# PiTopUSBHub_UB.net
KiCad netlist of a schematic drawn in Altium Designer
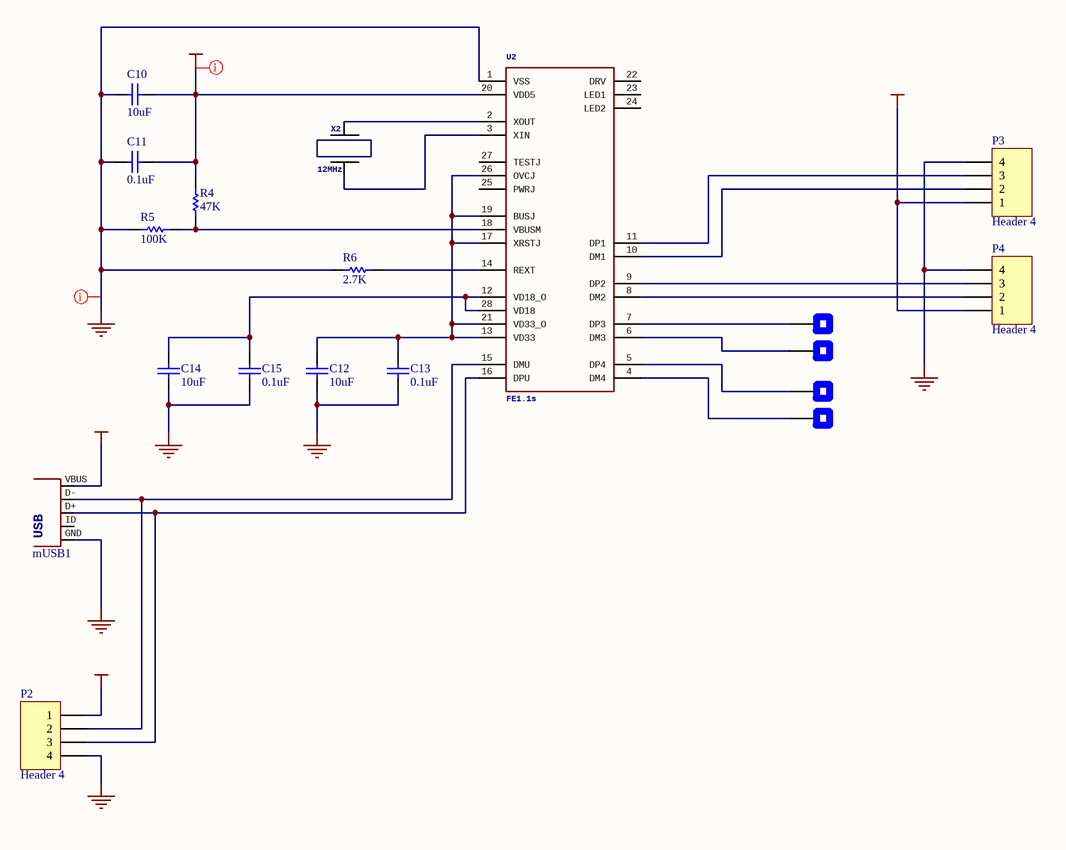
[diagram p0: PiTopUSBHub_UB.SchDoc]

(export (version "E")
  (design (tool "Eeschema 10.0.6"))
  (components
    (comp (ref "C10")
      (value "10uF")
      (footprint "C0805")
      (description "Ceramic Chip Capacitor - Standard")
      (fields (field (name "Comment") "C0805") (field (name "PUBLISHER") "Altium Limited"))
      (libsource (lib "KEMET Chip Capacitor") (part "C0805"))
    )
    (comp (ref "C11")
      (value "0.1uF")
      (footprint "C0805")
      (description "Ceramic Chip Capacitor - Standard")
      (fields (field (name "Comment") "C0805") (field (name "PUBLISHER") "Altium Limited"))
      (libsource (lib "KEMET Chip Capacitor") (part "C0805"))
    )
    (comp (ref "C12")
      (value "10uF")
      (footprint "C0805")
      (description "Ceramic Chip Capacitor - Standard")
      (fields (field (name "Comment") "C0805") (field (name "PUBLISHER") "Altium Limited"))
      (libsource (lib "KEMET Chip Capacitor") (part "C0805"))
    )
    (comp (ref "C13")
      (value "0.1uF")
      (footprint "C0805")
      (description "Ceramic Chip Capacitor - Standard")
      (fields (field (name "Comment") "C0805") (field (name "PUBLISHER") "Altium Limited"))
      (libsource (lib "KEMET Chip Capacitor") (part "C0805"))
    )
    (comp (ref "C14")
      (value "10uF")
      (footprint "C0805")
      (description "Ceramic Chip Capacitor - Standard")
      (fields (field (name "Comment") "C0805") (field (name "PUBLISHER") "Altium Limited"))
      (libsource (lib "KEMET Chip Capacitor") (part "C0805"))
    )
    (comp (ref "C15")
      (value "0.1uF")
      (footprint "C0805")
      (description "Ceramic Chip Capacitor - Standard")
      (fields (field (name "Comment") "C0805") (field (name "PUBLISHER") "Altium Limited"))
      (libsource (lib "KEMET Chip Capacitor") (part "C0805"))
    )
    (comp (ref "mUSB1")
      (value "miniUSB-PTH")
      (footprint "miniUSB-F-PTH")
      (fields (field (name "USB") "USB"))
      (libsource (lib "lib") (part "miniUSBA-PTH"))
    )
    (comp (ref "P2")
      (value "Header 4")
      (footprint "HDR1X4")
      (description "Header, 4-Pin")
      (fields (field (name "PUBLISHER") "Altium Limited"))
      (libsource (lib "") (part "Header 4_1"))
    )
    (comp (ref "P3")
      (value "Header 4")
      (footprint "HDR1X4")
      (description "Header, 4-Pin")
      (fields (field (name "PUBLISHER") "Altium Limited"))
      (libsource (lib "Miscellaneous Connectors") (part "Header 4"))
    )
    (comp (ref "P4")
      (value "Header 4")
      (footprint "HDR1X4")
      (description "Header, 4-Pin")
      (fields (field (name "PUBLISHER") "Altium Limited"))
      (libsource (lib "Miscellaneous Connectors") (part "Header 4"))
    )
    (comp (ref "R4")
      (value "47K")
      (footprint "R0805")
      (fields (field (name "PUBLISHER") "Altium Limited"))
      (libsource (lib "lib") (part "R0805"))
    )
    (comp (ref "R5")
      (value "100K")
      (footprint "R0805")
      (fields (field (name "PUBLISHER") "Altium Limited"))
      (libsource (lib "lib") (part "R0805"))
    )
    (comp (ref "R6")
      (value "2.7K")
      (footprint "R0805")
      (fields (field (name "PUBLISHER") "Altium Limited"))
      (libsource (lib "lib") (part "R0805"))
    )
    (comp (ref "TP1") (value "TP") (footprint "TP") (libsource (lib "lib") (part "TP")))
    (comp (ref "TP2") (value "TP") (footprint "TP") (libsource (lib "lib") (part "TP")))
    (comp (ref "TP3") (value "TP") (footprint "TP") (libsource (lib "lib") (part "TP")))
    (comp (ref "TP4") (value "TP") (footprint "TP") (libsource (lib "lib") (part "TP")))
    (comp (ref "U2")
      (value "FE1.1S")
      (footprint "FE1.1S_SSOP-28")
      (fields (field (name "FE1.1S") "FE1.1s"))
      (libsource (lib "lib") (part "FE1.1S"))
    )
    (comp (ref "X2")
      (value "12MHz")
      (footprint "XTAL_G5032")
      (description "PTH: ...   SMD: ...   Cylinder: CMR200T-32.768KDZBT")
      (libsource (lib "lib") (part "CRYSTALHC49UP"))
    )
  )
  (nets
    (net (code "1") (name "GND") (class "Default")
      (node (ref "C10") (pin "2") (pinfunction "2_2") (pintype "passive"))
      (node (ref "C11") (pin "2") (pinfunction "2_2") (pintype "passive"))
      (node (ref "C12") (pin "2") (pinfunction "2_2") (pintype "passive"))
      (node (ref "C13") (pin "2") (pinfunction "2_2") (pintype "passive"))
      (node (ref "C14") (pin "2") (pinfunction "2_2") (pintype "passive"))
      (node (ref "C15") (pin "2") (pinfunction "2_2") (pintype "passive"))
      (node (ref "P2") (pin "4") (pinfunction "4_4") (pintype "passive"))
      (node (ref "P3") (pin "4") (pinfunction "4_4") (pintype "passive"))
      (node (ref "P4") (pin "4") (pinfunction "4_4") (pintype "passive"))
      (node (ref "R5") (pin "2") (pinfunction "2_2") (pintype "passive"))
      (node (ref "R6") (pin "1") (pinfunction "1_1") (pintype "passive"))
      (node (ref "U2") (pin "1") (pinfunction "VSS_1") (pintype "passive"))
      (node (ref "mUSB1") (pin "GND") (pinfunction "GND_GND") (pintype "passive"))
    )
    (net (code "2") (name "Net-(U2-BUSJ)") (class "Default")
      (node (ref "C12") (pin "1") (pinfunction "1_1") (pintype "passive"))
      (node (ref "C13") (pin "1") (pinfunction "1_1") (pintype "passive"))
      (node (ref "U2") (pin "13") (pinfunction "VD33_13") (pintype "passive"))
      (node (ref "U2") (pin "17") (pinfunction "XRSTJ_17") (pintype "passive"))
      (node (ref "U2") (pin "19") (pinfunction "BUSJ_19") (pintype "passive"))
      (node (ref "U2") (pin "21") (pinfunction "VD33_O_21") (pintype "passive"))
      (node (ref "U2") (pin "26") (pinfunction "OVCJ_26") (pintype "passive"))
    )
    (net (code "3") (name "Net-(U2-DM1)") (class "Default")
      (node (ref "P3") (pin "2") (pinfunction "2_2") (pintype "passive"))
      (node (ref "U2") (pin "10") (pinfunction "DM1_10") (pintype "passive"))
    )
    (net (code "4") (name "Net-(U2-DM2)") (class "Default")
      (node (ref "P4") (pin "2") (pinfunction "2_2") (pintype "passive"))
      (node (ref "U2") (pin "8") (pinfunction "DM2_8") (pintype "passive"))
    )
    (net (code "5") (name "Net-(U2-DM3)") (class "Default")
      (node (ref "TP2") (pin "1") (pinfunction "1_1") (pintype "passive"))
      (node (ref "U2") (pin "6") (pinfunction "DM3_6") (pintype "passive"))
    )
    (net (code "6") (name "Net-(U2-DM4)") (class "Default")
      (node (ref "TP4") (pin "1") (pinfunction "1_1") (pintype "passive"))
      (node (ref "U2") (pin "4") (pinfunction "DM4_4") (pintype "passive"))
    )
    (net (code "7") (name "Net-(U2-DMU)") (class "Default")
      (node (ref "P2") (pin "2") (pinfunction "2_2") (pintype "passive"))
      (node (ref "U2") (pin "15") (pinfunction "DMU_15") (pintype "passive"))
      (node (ref "mUSB1") (pin "D-") (pinfunction "D-_D-") (pintype "passive"))
    )
    (net (code "8") (name "Net-(U2-DP1)") (class "Default")
      (node (ref "P3") (pin "3") (pinfunction "3_3") (pintype "passive"))
      (node (ref "U2") (pin "11") (pinfunction "DP1_11") (pintype "passive"))
    )
    (net (code "9") (name "Net-(U2-DP2)") (class "Default")
      (node (ref "P4") (pin "3") (pinfunction "3_3") (pintype "passive"))
      (node (ref "U2") (pin "9") (pinfunction "DP2_9") (pintype "passive"))
    )
    (net (code "10") (name "Net-(U2-DP3)") (class "Default")
      (node (ref "TP1") (pin "1") (pinfunction "1_1") (pintype "passive"))
      (node (ref "U2") (pin "7") (pinfunction "DP3_7") (pintype "passive"))
    )
    (net (code "11") (name "Net-(U2-DP4)") (class "Default")
      (node (ref "TP3") (pin "1") (pinfunction "1_1") (pintype "passive"))
      (node (ref "U2") (pin "5") (pinfunction "DP4_5") (pintype "passive"))
    )
    (net (code "12") (name "Net-(U2-DPU)") (class "Default")
      (node (ref "P2") (pin "3") (pinfunction "3_3") (pintype "passive"))
      (node (ref "U2") (pin "16") (pinfunction "DPU_16") (pintype "passive"))
      (node (ref "mUSB1") (pin "D+") (pinfunction "D+_D+") (pintype "passive"))
    )
    (net (code "13") (name "Net-(U2-REXT)") (class "Default")
      (node (ref "R6") (pin "2") (pinfunction "2_2") (pintype "passive"))
      (node (ref "U2") (pin "14") (pinfunction "REXT_14") (pintype "passive"))
    )
    (net (code "14") (name "Net-(U2-VBUSM)") (class "Default")
      (node (ref "R4") (pin "2") (pinfunction "2_2") (pintype "passive"))
      (node (ref "R5") (pin "1") (pinfunction "1_1") (pintype "passive"))
      (node (ref "U2") (pin "18") (pinfunction "VBUSM_18") (pintype "passive"))
    )
    (net (code "15") (name "Net-(U2-VD18)") (class "Default")
      (node (ref "C14") (pin "1") (pinfunction "1_1") (pintype "passive"))
      (node (ref "C15") (pin "1") (pinfunction "1_1") (pintype "passive"))
      (node (ref "U2") (pin "12") (pinfunction "VD18_O_12") (pintype "passive"))
      (node (ref "U2") (pin "28") (pinfunction "VD18_28") (pintype "passive"))
    )
    (net (code "16") (name "Net-(U2-XIN)") (class "Default")
      (node (ref "U2") (pin "3") (pinfunction "XIN_3") (pintype "passive"))
      (node (ref "X2") (pin "1") (pinfunction "1_1") (pintype "passive"))
    )
    (net (code "17") (name "Net-(U2-XOUT)") (class "Default")
      (node (ref "U2") (pin "2") (pinfunction "XOUT_2") (pintype "passive"))
      (node (ref "X2") (pin "2") (pinfunction "2_2") (pintype "passive"))
    )
    (net (code "18") (name "VCC2") (class "Default")
      (node (ref "C10") (pin "1") (pinfunction "1_1") (pintype "passive"))
      (node (ref "C11") (pin "1") (pinfunction "1_1") (pintype "passive"))
      (node (ref "P2") (pin "1") (pinfunction "1_1") (pintype "passive"))
      (node (ref "P3") (pin "1") (pinfunction "1_1") (pintype "passive"))
      (node (ref "P4") (pin "1") (pinfunction "1_1") (pintype "passive"))
      (node (ref "R4") (pin "1") (pinfunction "1_1") (pintype "passive"))
      (node (ref "U2") (pin "20") (pinfunction "VDD5_20") (pintype "passive"))
      (node (ref "mUSB1") (pin "VBUS") (pinfunction "VBUS_VBUS") (pintype "passive"))
    )
    (net (code "19") (name "unconnected-(U2-DRV-Pad22)") (class "Default")
      (node (ref "U2") (pin "22") (pinfunction "DRV_22") (pintype "passive"))
    )
    (net (code "20") (name "unconnected-(U2-LED1-Pad23)") (class "Default")
      (node (ref "U2") (pin "23") (pinfunction "LED1_23") (pintype "passive"))
    )
    (net (code "21") (name "unconnected-(U2-LED2-Pad24)") (class "Default")
      (node (ref "U2") (pin "24") (pinfunction "LED2_24") (pintype "passive"))
    )
    (net (code "22") (name "unconnected-(U2-PWRJ-Pad25)") (class "Default")
      (node (ref "U2") (pin "25") (pinfunction "PWRJ_25") (pintype "passive"))
    )
    (net (code "23") (name "unconnected-(U2-TESTJ-Pad27)") (class "Default")
      (node (ref "U2") (pin "27") (pinfunction "TESTJ_27") (pintype "passive"))
    )
    (net (code "24") (name "unconnected-(mUSB1-PadID)") (class "Default")
      (node (ref "mUSB1") (pin "ID") (pinfunction "ID_ID") (pintype "passive"))
    )
  )
)
